# CLK_buffer_DRTIO_CDR.net
KiCad netlist of a schematic drawn in Altium Designer
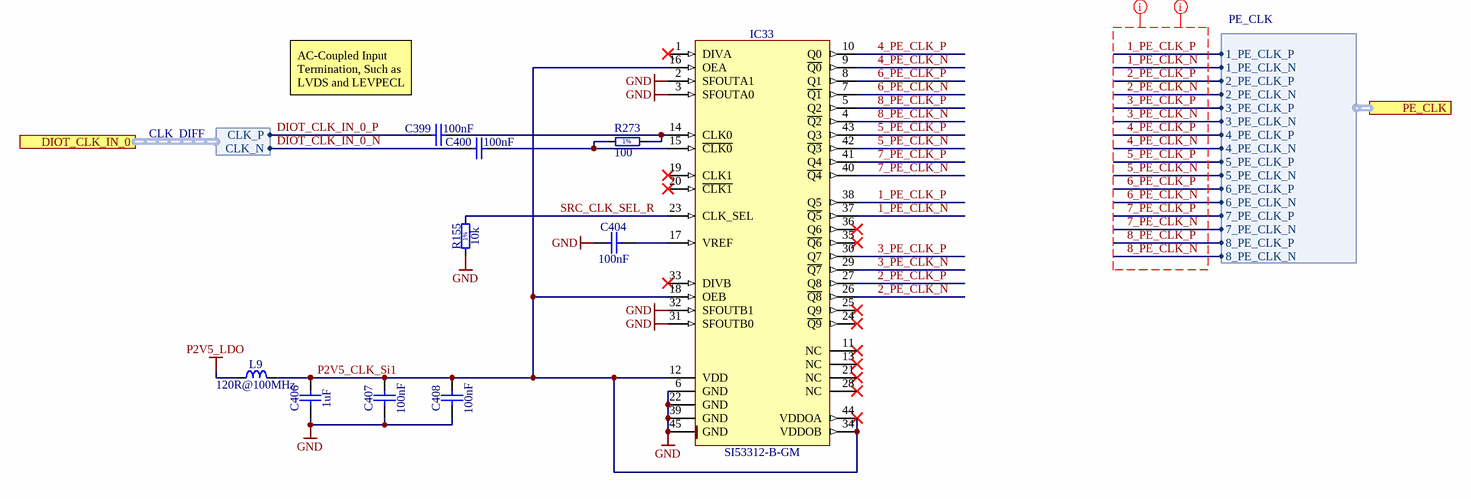
[diagram p0: CLK_buffer_DRTIO_CDR.SchDoc]

(export (version "E")
  (design (tool "Eeschema 10.0.6"))
  (components
    (comp (ref "C399")
      (value "100nF")
      (footprint "CAPC0603X33N")
      (description "Non-polarised capacitor")
      (fields
        (field (name "PART NUMBER") "CC0201_100NF_6.3V_10%_X5R")
        (field (name "VOLTAGE") "6.3V")
        (field (name "AUTHOR") "CERN DEM JLC")
      )
      (libsource (lib "Capacitors") (part "Capacitor - non polarized"))
    )
    (comp (ref "C400")
      (value "100nF")
      (footprint "CAPC0603X33N")
      (description "Non-polarised capacitor")
      (fields
        (field (name "PART NUMBER") "CC0201_100NF_6.3V_10%_X5R")
        (field (name "VOLTAGE") "6.3V")
        (field (name "AUTHOR") "CERN DEM JLC")
      )
      (libsource (lib "Capacitors") (part "Capacitor - non polarized"))
    )
    (comp (ref "C404")
      (value "100nF")
      (footprint "CAPC1005X55N")
      (description "Non-polarised capacitor")
      (fields
        (field (name "PART NUMBER") "CC0402_100NF_16V_10%_X7R")
        (field (name "VOLTAGE") "16V")
        (field (name "AUTHOR") "CERN DEM JLC")
      )
      (libsource (lib "Capacitors") (part "Capacitor - non polarized"))
    )
    (comp (ref "C406")
      (value "1uF")
      (footprint "CAPC1608X87N")
      (description "Non-polarised capacitor")
      (fields
        (field (name "PART NUMBER") "CC0603_1UF_25V_10%_X7R")
        (field (name "VOLTAGE") "25V")
        (field (name "AUTHOR") "CERN DEM JLC")
      )
      (libsource (lib "Capacitors") (part "Capacitor - non polarized"))
    )
    (comp (ref "C407")
      (value "100nF")
      (footprint "CAPC1005X55N")
      (description "Non-polarised capacitor")
      (fields
        (field (name "PART NUMBER") "CC0402_100NF_16V_10%_X7R")
        (field (name "VOLTAGE") "16V")
        (field (name "AUTHOR") "CERN DEM JLC")
      )
      (libsource (lib "Capacitors") (part "Capacitor - non polarized"))
    )
    (comp (ref "C408")
      (value "100nF")
      (footprint "CAPC1005X55N")
      (description "Non-polarised capacitor")
      (fields
        (field (name "PART NUMBER") "CC0402_100NF_16V_10%_X7R")
        (field (name "VOLTAGE") "16V")
        (field (name "AUTHOR") "CERN DEM JLC")
      )
      (libsource (lib "Capacitors") (part "Capacitor - non polarized"))
    )
    (comp (ref "IC33")
      (value "SI53312-B-GM")
      (footprint "QFN50P700X700X90-45N-S295")
      (description "2 Input/10 Output, Low Jitter Universal Buffer/Level Translator With 2:1 Input Mux (<1.25 GHZ)")
      (fields (field (name "MANUFACTURER") "SILICON LABS") (field (name "AUTHOR") "CERN DEM MR"))
      (libsource (lib "ICs And Semiconductors") (part "SI53312"))
    )
    (comp (ref "L9")
      (value "120R@100MHz")
      (footprint "INDC1608X95N")
      (description "Inductor")
      (fields
        (field (name "PART NUMBER") "IND0603_MURATA_BLM18PG121SN1D")
        (field (name "POWER") "2A")
        (field (name "AUTHOR") "CERN DEM BC")
      )
      (libsource (lib "Inductors & Transformers") (part "Inductor"))
    )
    (comp (ref "R155")
      (value "10k")
      (footprint "RESC1005X40N")
      (description "Resistor - 1%")
      (fields
        (field (name "PART NUMBER") "R0402_10K_1%_0.0625W_100PPM")
        (field (name "POWER") "0.0625W")
        (field (name "AUTHOR") "CERN DEM JLC")
      )
      (libsource (lib "Resistors") (part "Resistor - 1%"))
    )
    (comp (ref "R273")
      (value "100")
      (footprint "RESC1005X40N")
      (description "Resistor - 1%")
      (fields
        (field (name "PART NUMBER") "R0402_100R_1%_0.0625W_100PPM")
        (field (name "POWER") "0.0625W")
        (field (name "AUTHOR") "CERN DEM JLC")
      )
      (libsource (lib "Resistors") (part "Resistor - 1%"))
    )
  )
  (nets
    (net (code "3") (name "/1_PE_CLK_N") (class "Default")
      (node (ref "IC33") (pin "37") (pinfunction "~{Q5}_37") (pintype "output"))
    )
    (net (code "4") (name "/1_PE_CLK_P") (class "Default")
      (node (ref "IC33") (pin "38") (pinfunction "Q5_38") (pintype "output"))
    )
    (net (code "5") (name "/2_PE_CLK_N") (class "Default")
      (node (ref "IC33") (pin "26") (pinfunction "~{Q8}_26") (pintype "output"))
    )
    (net (code "6") (name "/2_PE_CLK_P") (class "Default")
      (node (ref "IC33") (pin "27") (pinfunction "Q8_27") (pintype "output"))
    )
    (net (code "7") (name "/3_PE_CLK_N") (class "Default")
      (node (ref "IC33") (pin "29") (pinfunction "~{Q7}_29") (pintype "output"))
    )
    (net (code "8") (name "/3_PE_CLK_P") (class "Default")
      (node (ref "IC33") (pin "30") (pinfunction "Q7_30") (pintype "output"))
    )
    (net (code "9") (name "/4_PE_CLK_N") (class "Default")
      (node (ref "IC33") (pin "9") (pinfunction "~{Q0}_9") (pintype "output"))
    )
    (net (code "10") (name "/4_PE_CLK_P") (class "Default")
      (node (ref "IC33") (pin "10") (pinfunction "Q0_10") (pintype "output"))
    )
    (net (code "11") (name "/5_PE_CLK_N") (class "Default")
      (node (ref "IC33") (pin "42") (pinfunction "~{Q3}_42") (pintype "output"))
    )
    (net (code "12") (name "/5_PE_CLK_P") (class "Default")
      (node (ref "IC33") (pin "43") (pinfunction "Q3_43") (pintype "output"))
    )
    (net (code "13") (name "/6_PE_CLK_N") (class "Default")
      (node (ref "IC33") (pin "7") (pinfunction "~{Q1}_7") (pintype "output"))
    )
    (net (code "14") (name "/6_PE_CLK_P") (class "Default")
      (node (ref "IC33") (pin "8") (pinfunction "Q1_8") (pintype "output"))
    )
    (net (code "15") (name "/7_PE_CLK_N") (class "Default")
      (node (ref "IC33") (pin "40") (pinfunction "~{Q4}_40") (pintype "output"))
    )
    (net (code "16") (name "/7_PE_CLK_P") (class "Default")
      (node (ref "IC33") (pin "41") (pinfunction "Q4_41") (pintype "output"))
    )
    (net (code "17") (name "/8_PE_CLK_N") (class "Default")
      (node (ref "IC33") (pin "4") (pinfunction "~{Q2}_4") (pintype "output"))
    )
    (net (code "18") (name "/8_PE_CLK_P") (class "Default")
      (node (ref "IC33") (pin "5") (pinfunction "Q2_5") (pintype "output"))
    )
    (net (code "19") (name "/DIOT_CLK_IN_0_N") (class "Default")
      (node (ref "C400") (pin "1") (pinfunction "1_1") (pintype "passive"))
    )
    (net (code "20") (name "/DIOT_CLK_IN_0_P") (class "Default")
      (node (ref "C399") (pin "1") (pinfunction "1_1") (pintype "passive"))
    )
    (net (code "21") (name "/P2V5_CLK_Si1") (class "Default")
      (node (ref "C406") (pin "2") (pinfunction "2_2") (pintype "passive"))
      (node (ref "C407") (pin "2") (pinfunction "2_2") (pintype "passive"))
      (node (ref "C408") (pin "2") (pinfunction "2_2") (pintype "passive"))
      (node (ref "IC33") (pin "12") (pinfunction "VDD_12") (pintype "power_in"))
      (node (ref "IC33") (pin "16") (pinfunction "OEA_16") (pintype "input"))
      (node (ref "IC33") (pin "18") (pinfunction "OEB_18") (pintype "input"))
      (node (ref "IC33") (pin "34") (pinfunction "VDDOB_34") (pintype "output"))
      (node (ref "IC33") (pin "44") (pinfunction "VDDOA_44") (pintype "output"))
      (node (ref "L9") (pin "1") (pinfunction "1_1") (pintype "passive"))
    )
    (net (code "22") (name "/SRC_CLK_SEL_R") (class "Default")
      (node (ref "IC33") (pin "23") (pinfunction "CLK_SEL_23") (pintype "input"))
      (node (ref "R155") (pin "2") (pinfunction "2_2") (pintype "passive"))
    )
    (net (code "25") (name "GND") (class "Default")
      (node (ref "C404") (pin "1") (pinfunction "1_1") (pintype "passive"))
      (node (ref "C406") (pin "1") (pinfunction "1_1") (pintype "passive"))
      (node (ref "C407") (pin "1") (pinfunction "1_1") (pintype "passive"))
      (node (ref "C408") (pin "1") (pinfunction "1_1") (pintype "passive"))
      (node (ref "IC33") (pin "2") (pinfunction "SFOUTA1_2") (pintype "input"))
      (node (ref "IC33") (pin "22") (pinfunction "GND_22") (pintype "power_in"))
      (node (ref "IC33") (pin "3") (pinfunction "SFOUTA0_3") (pintype "input"))
      (node (ref "IC33") (pin "31") (pinfunction "SFOUTB0_31") (pintype "input"))
      (node (ref "IC33") (pin "32") (pinfunction "SFOUTB1_32") (pintype "input"))
      (node (ref "IC33") (pin "39") (pinfunction "GND_39") (pintype "power_in"))
      (node (ref "IC33") (pin "45") (pinfunction "GND_45") (pintype "power_in"))
      (node (ref "IC33") (pin "6") (pinfunction "GND_6") (pintype "power_in"))
      (node (ref "R155") (pin "1") (pinfunction "1_1") (pintype "passive"))
    )
    (net (code "26") (name "Net-(IC33-CLK0)") (class "Default")
      (node (ref "C399") (pin "2") (pinfunction "2_2") (pintype "passive"))
      (node (ref "IC33") (pin "14") (pinfunction "CLK0_14") (pintype "input"))
      (node (ref "R273") (pin "2") (pinfunction "2_2") (pintype "passive"))
    )
    (net (code "27") (name "Net-(IC33-VREF)") (class "Default")
      (node (ref "C404") (pin "2") (pinfunction "2_2") (pintype "passive"))
      (node (ref "IC33") (pin "17") (pinfunction "VREF_17") (pintype "input"))
    )
    (net (code "28") (name "Net-(IC33-~{CLK0})") (class "Default")
      (node (ref "C400") (pin "2") (pinfunction "2_2") (pintype "passive"))
      (node (ref "IC33") (pin "15") (pinfunction "~{CLK0}_15") (pintype "input"))
      (node (ref "R273") (pin "1") (pinfunction "1_1") (pintype "passive"))
    )
    (net (code "29") (name "P2V5_LDO") (class "Default")
      (node (ref "L9") (pin "2") (pinfunction "2_2") (pintype "passive"))
    )
    (net (code "30") (name "unconnected-(IC33-CLK1-Pad19)") (class "Default")
      (node (ref "IC33") (pin "19") (pinfunction "CLK1_19") (pintype "input+no_connect"))
    )
    (net (code "31") (name "unconnected-(IC33-DIVA-Pad1)") (class "Default")
      (node (ref "IC33") (pin "1") (pinfunction "DIVA_1") (pintype "input+no_connect"))
    )
    (net (code "32") (name "unconnected-(IC33-DIVB-Pad33)") (class "Default")
      (node (ref "IC33") (pin "33") (pinfunction "DIVB_33") (pintype "input+no_connect"))
    )
    (net (code "33") (name "unconnected-(IC33-NC-Pad11)") (class "Default")
      (node (ref "IC33") (pin "11") (pinfunction "NC_11") (pintype "passive+no_connect"))
    )
    (net (code "34") (name "unconnected-(IC33-NC-Pad13)") (class "Default")
      (node (ref "IC33") (pin "13") (pinfunction "NC_13") (pintype "passive+no_connect"))
    )
    (net (code "35") (name "unconnected-(IC33-NC-Pad21)") (class "Default")
      (node (ref "IC33") (pin "21") (pinfunction "NC_21") (pintype "passive+no_connect"))
    )
    (net (code "36") (name "unconnected-(IC33-NC-Pad28)") (class "Default")
      (node (ref "IC33") (pin "28") (pinfunction "NC_28") (pintype "passive+no_connect"))
    )
    (net (code "37") (name "unconnected-(IC33-Q6-Pad36)") (class "Default")
      (node (ref "IC33") (pin "36") (pinfunction "Q6_36") (pintype "output+no_connect"))
    )
    (net (code "38") (name "unconnected-(IC33-Q9-Pad25)") (class "Default")
      (node (ref "IC33") (pin "25") (pinfunction "Q9_25") (pintype "output+no_connect"))
    )
    (net (code "39") (name "unconnected-(IC33-~{CLK1}-Pad20)") (class "Default")
      (node (ref "IC33") (pin "20") (pinfunction "~{CLK1}_20") (pintype "input+no_connect"))
    )
    (net (code "40") (name "unconnected-(IC33-~{Q6}-Pad35)") (class "Default")
      (node (ref "IC33") (pin "35") (pinfunction "~{Q6}_35") (pintype "output+no_connect"))
    )
    (net (code "41") (name "unconnected-(IC33-~{Q9}-Pad24)") (class "Default")
      (node (ref "IC33") (pin "24") (pinfunction "~{Q9}_24") (pintype "output+no_connect"))
    )
  )
)
